# alimentadorV3.net
KiCad netlist of a schematic drawn in EAGLE
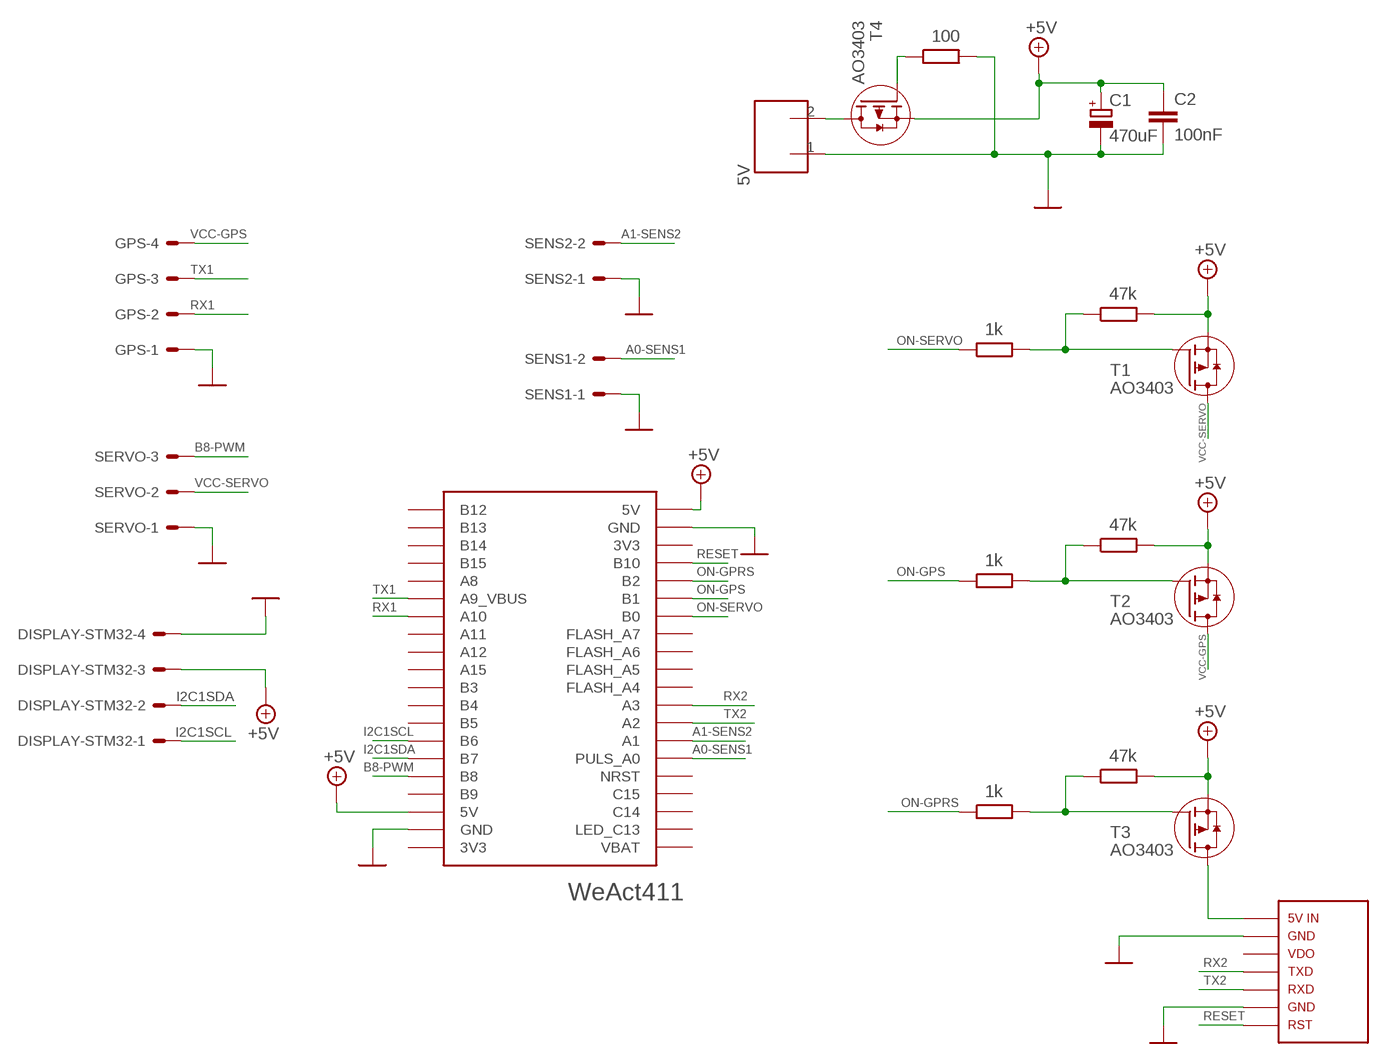
[diagram p0: schematic, sheet 1]

(export (version "E")
  (design (tool "Eeschema 10.0.6"))
  (components
    (comp (ref "5V")
      (value "CONECTOR_2P-3.81")
      (footprint "eagle-import:CON2P-3.81")
      (libsource (lib "eagle-import") (part "CONECTOR_2P-3.81"))
    )
    (comp (ref "C1")
      (value "470uF")
      (footprint "eagle-import:E5-10,5")
      (libsource (lib "eagle-import") (part "CPOL-EUE5-10.5"))
    )
    (comp (ref "C2")
      (value "100nF")
      (footprint "eagle-import:C1206")
      (libsource (lib "eagle-import") (part "C-EUC1206"))
    )
    (comp (ref "DISPLAY-STM32")
      (value "22-05-7048-04")
      (footprint "eagle-import:7395-04")
      (libsource (lib "eagle-import") (part "22-?-0405-7048"))
    )
    (comp (ref "GPS")
      (value "22-27-2041-04")
      (footprint "eagle-import:6410-04")
      (libsource (lib "eagle-import") (part "22-?-0427-2041"))
    )
    (comp (ref "R1")
      (value "47k")
      (footprint "eagle-import:R1206")
      (libsource (lib "eagle-import") (part "R-EU_R1206"))
    )
    (comp (ref "R2")
      (value "47k")
      (footprint "eagle-import:R1206")
      (libsource (lib "eagle-import") (part "R-EU_R1206"))
    )
    (comp (ref "R3")
      (value "1k")
      (footprint "eagle-import:R1206")
      (libsource (lib "eagle-import") (part "R-EU_R1206"))
    )
    (comp (ref "R4")
      (value "1k")
      (footprint "eagle-import:R1206")
      (libsource (lib "eagle-import") (part "R-EU_R1206"))
    )
    (comp (ref "R5")
      (value "47k")
      (footprint "eagle-import:R1206")
      (libsource (lib "eagle-import") (part "R-EU_R1206"))
    )
    (comp (ref "R6")
      (value "1k")
      (footprint "eagle-import:R1206")
      (libsource (lib "eagle-import") (part "R-EU_R1206"))
    )
    (comp (ref "R7")
      (value "100")
      (footprint "eagle-import:R1206")
      (libsource (lib "eagle-import") (part "R-EU_R1206"))
    )
    (comp (ref "SENS1")
      (value "22-27-2021-02")
      (footprint "eagle-import:6410-02")
      (libsource (lib "eagle-import") (part "22-?-0227-2021"))
    )
    (comp (ref "SENS2")
      (value "22-27-2021-02")
      (footprint "eagle-import:6410-02")
      (libsource (lib "eagle-import") (part "22-?-0227-2021"))
    )
    (comp (ref "SERVO")
      (value "22-27-2031-03")
      (footprint "eagle-import:6410-03")
      (libsource (lib "eagle-import") (part "22-?-0327-2031"))
    )
    (comp (ref "T1")
      (value "AO3403")
      (footprint "eagle-import:SOT23")
      (libsource (lib "eagle-import") (part "AO3403"))
    )
    (comp (ref "T2")
      (value "AO3403")
      (footprint "eagle-import:SOT23")
      (libsource (lib "eagle-import") (part "AO3403"))
    )
    (comp (ref "T3")
      (value "AO3403")
      (footprint "eagle-import:SOT23")
      (libsource (lib "eagle-import") (part "AO3403"))
    )
    (comp (ref "T4")
      (value "AO3403")
      (footprint "eagle-import:SOT23")
      (libsource (lib "eagle-import") (part "AO3403"))
    )
    (comp (ref "U$1")
      (value "SIM800L")
      (footprint "eagle-import:SIM800L")
      (libsource (lib "eagle-import") (part "SIM800L"))
    )
    (comp (ref "U$2")
      (value "WEACT411")
      (footprint "eagle-import:WEACT411")
      (libsource (lib "eagle-import") (part "WEACT411"))
    )
  )
  (nets
    (net (code "1") (name "+5V") (class "Default")
      (node (ref "C1") (pin "+") (pinfunction "+_+") (pintype "passive"))
      (node (ref "C2") (pin "1") (pinfunction "1_1") (pintype "passive"))
      (node (ref "DISPLAY-STM32") (pin "3") (pinfunction "S_3") (pintype "passive"))
      (node (ref "R1") (pin "2") (pinfunction "2_2") (pintype "passive"))
      (node (ref "R2") (pin "2") (pinfunction "2_2") (pintype "passive"))
      (node (ref "R5") (pin "2") (pinfunction "2_2") (pintype "passive"))
      (node (ref "T1") (pin "2") (pinfunction "S_2") (pintype "passive"))
      (node (ref "T2") (pin "2") (pinfunction "S_2") (pintype "passive"))
      (node (ref "T3") (pin "2") (pinfunction "S_2") (pintype "passive"))
      (node (ref "T4") (pin "2") (pinfunction "S_2") (pintype "passive"))
      (node (ref "U$2") (pin "5V@1") (pinfunction "5V_5V@1") (pintype "power_in"))
      (node (ref "U$2") (pin "5V@2") (pinfunction "5V_5V@2") (pintype "power_in"))
    )
    (net (code "2") (name "/A0-SENS1") (class "Default")
      (node (ref "SENS1") (pin "2") (pinfunction "S_2") (pintype "passive"))
      (node (ref "U$2") (pin "A0") (pinfunction "PULS_A0_A0") (pintype "bidirectional"))
    )
    (net (code "3") (name "/A1-SENS2") (class "Default")
      (node (ref "SENS2") (pin "2") (pinfunction "S_2") (pintype "passive"))
      (node (ref "U$2") (pin "A1") (pinfunction "A1_A1") (pintype "bidirectional"))
    )
    (net (code "4") (name "/B8-PWM") (class "Default")
      (node (ref "SERVO") (pin "3") (pinfunction "S_3") (pintype "passive"))
      (node (ref "U$2") (pin "B8") (pinfunction "B8_B8") (pintype "bidirectional"))
    )
    (net (code "5") (name "/I2C1SCL") (class "Default")
      (node (ref "DISPLAY-STM32") (pin "1") (pinfunction "S_1") (pintype "passive"))
      (node (ref "U$2") (pin "B6") (pinfunction "B6_B6") (pintype "bidirectional"))
    )
    (net (code "6") (name "/I2C1SDA") (class "Default")
      (node (ref "DISPLAY-STM32") (pin "2") (pinfunction "S_2") (pintype "passive"))
      (node (ref "U$2") (pin "B7") (pinfunction "B7_B7") (pintype "bidirectional"))
    )
    (net (code "7") (name "/ON-GPRS") (class "Default")
      (node (ref "R6") (pin "1") (pinfunction "1_1") (pintype "passive"))
      (node (ref "U$2") (pin "B2") (pinfunction "B2_B2") (pintype "bidirectional"))
    )
    (net (code "8") (name "/ON-GPS") (class "Default")
      (node (ref "R4") (pin "1") (pinfunction "1_1") (pintype "passive"))
      (node (ref "U$2") (pin "B1") (pinfunction "B1_B1") (pintype "bidirectional"))
    )
    (net (code "9") (name "/ON-SERVO") (class "Default")
      (node (ref "R3") (pin "1") (pinfunction "1_1") (pintype "passive"))
      (node (ref "U$2") (pin "B0") (pinfunction "B0_B0") (pintype "bidirectional"))
    )
    (net (code "10") (name "/RESET") (class "Default")
      (node (ref "U$1") (pin "RST") (pinfunction "RST_RST") (pintype "input"))
      (node (ref "U$2") (pin "B10") (pinfunction "B10_B10") (pintype "bidirectional"))
    )
    (net (code "11") (name "/RX1") (class "Default")
      (node (ref "GPS") (pin "2") (pinfunction "S_2") (pintype "passive"))
      (node (ref "U$2") (pin "A10") (pinfunction "A10_A10") (pintype "bidirectional"))
    )
    (net (code "12") (name "/RX2") (class "Default")
      (node (ref "U$1") (pin "TXD") (pinfunction "TXD_TXD") (pintype "output"))
      (node (ref "U$2") (pin "A3") (pinfunction "A3_A3") (pintype "bidirectional"))
    )
    (net (code "13") (name "/TX1") (class "Default")
      (node (ref "GPS") (pin "3") (pinfunction "S_3") (pintype "passive"))
      (node (ref "U$2") (pin "A9") (pinfunction "A9_VBUS_A9") (pintype "bidirectional"))
    )
    (net (code "14") (name "/TX2") (class "Default")
      (node (ref "U$1") (pin "RXD") (pinfunction "RXD_RXD") (pintype "input"))
      (node (ref "U$2") (pin "A2") (pinfunction "A2_A2") (pintype "bidirectional"))
    )
    (net (code "15") (name "/VBAT") (class "Default")
      (node (ref "U$2") (pin "VBAT") (pinfunction "VBAT_VBAT") (pintype "power_in"))
    )
    (net (code "16") (name "/VCC-GPS") (class "Default")
      (node (ref "GPS") (pin "4") (pinfunction "S_4") (pintype "passive"))
      (node (ref "T2") (pin "3") (pinfunction "D_3") (pintype "passive"))
    )
    (net (code "17") (name "/VCC-SERVO") (class "Default")
      (node (ref "SERVO") (pin "2") (pinfunction "S_2") (pintype "passive"))
      (node (ref "T1") (pin "3") (pinfunction "D_3") (pintype "passive"))
    )
    (net (code "18") (name "/VDO") (class "Default")
      (node (ref "U$1") (pin "VDO") (pinfunction "VDO_VDO") (pintype "power_in"))
    )
    (net (code "19") (name "GND") (class "Default")
      (node (ref "5V") (pin "1") (pinfunction "1_1") (pintype "bidirectional"))
      (node (ref "C1") (pin "-") (pinfunction "-_-") (pintype "passive"))
      (node (ref "C2") (pin "2") (pinfunction "2_2") (pintype "passive"))
      (node (ref "DISPLAY-STM32") (pin "4") (pinfunction "S_4") (pintype "passive"))
      (node (ref "GPS") (pin "1") (pinfunction "S_1") (pintype "passive"))
      (node (ref "R7") (pin "2") (pinfunction "2_2") (pintype "passive"))
      (node (ref "SENS1") (pin "1") (pinfunction "S_1") (pintype "passive"))
      (node (ref "SENS2") (pin "1") (pinfunction "S_1") (pintype "passive"))
      (node (ref "SERVO") (pin "1") (pinfunction "S_1") (pintype "passive"))
      (node (ref "U$1") (pin "GND@0") (pinfunction "GND_GND@0") (pintype "power_in"))
      (node (ref "U$1") (pin "GND@1") (pinfunction "GND_GND@1") (pintype "power_in"))
      (node (ref "U$2") (pin "GND@1") (pinfunction "GND_GND@1") (pintype "power_in"))
      (node (ref "U$2") (pin "GND@2") (pinfunction "GND_GND@2") (pintype "power_in"))
    )
    (net (code "20") (name "Net-(T1-G)") (class "Default")
      (node (ref "R2") (pin "1") (pinfunction "1_1") (pintype "passive"))
      (node (ref "R3") (pin "2") (pinfunction "2_2") (pintype "passive"))
      (node (ref "T1") (pin "1") (pinfunction "G_1") (pintype "passive"))
    )
    (net (code "21") (name "Net-(T2-G)") (class "Default")
      (node (ref "R1") (pin "1") (pinfunction "1_1") (pintype "passive"))
      (node (ref "R4") (pin "2") (pinfunction "2_2") (pintype "passive"))
      (node (ref "T2") (pin "1") (pinfunction "G_1") (pintype "passive"))
    )
    (net (code "22") (name "Net-(T3-D)") (class "Default")
      (node (ref "T3") (pin "3") (pinfunction "D_3") (pintype "passive"))
      (node (ref "U$1") (pin "5VIN") (pinfunction "5VIN_5VIN") (pintype "power_in"))
    )
    (net (code "23") (name "Net-(T3-G)") (class "Default")
      (node (ref "R5") (pin "1") (pinfunction "1_1") (pintype "passive"))
      (node (ref "R6") (pin "2") (pinfunction "2_2") (pintype "passive"))
      (node (ref "T3") (pin "1") (pinfunction "G_1") (pintype "passive"))
    )
    (net (code "24") (name "Net-(T4-D)") (class "Default")
      (node (ref "5V") (pin "2") (pinfunction "2_2") (pintype "bidirectional"))
      (node (ref "T4") (pin "3") (pinfunction "D_3") (pintype "passive"))
    )
    (net (code "25") (name "Net-(T4-G)") (class "Default")
      (node (ref "R7") (pin "1") (pinfunction "1_1") (pintype "passive"))
      (node (ref "T4") (pin "1") (pinfunction "G_1") (pintype "passive"))
    )
    (net (code "26") (name "unconnected-(U$2-3V3-Pad3V3@1)") (class "Default")
      (node (ref "U$2") (pin "3V3@1") (pinfunction "3V3_3V3@1") (pintype "bidirectional"))
    )
    (net (code "27") (name "unconnected-(U$2-3V3-Pad3V3@2)") (class "Default")
      (node (ref "U$2") (pin "3V3@2") (pinfunction "3V3_3V3@2") (pintype "bidirectional"))
    )
    (net (code "28") (name "unconnected-(U$2-FLASH_A4-PadA4)") (class "Default")
      (node (ref "U$2") (pin "A4") (pinfunction "FLASH_A4_A4") (pintype "bidirectional"))
    )
    (net (code "29") (name "unconnected-(U$2-FLASH_A5-PadA5)") (class "Default")
      (node (ref "U$2") (pin "A5") (pinfunction "FLASH_A5_A5") (pintype "bidirectional"))
    )
    (net (code "30") (name "unconnected-(U$2-FLASH_A6-PadA6)") (class "Default")
      (node (ref "U$2") (pin "A6") (pinfunction "FLASH_A6_A6") (pintype "bidirectional"))
    )
    (net (code "31") (name "unconnected-(U$2-FLASH_A7-PadA7)") (class "Default")
      (node (ref "U$2") (pin "A7") (pinfunction "FLASH_A7_A7") (pintype "bidirectional"))
    )
    (net (code "32") (name "unconnected-(U$2-LED_C13-PadC13)") (class "Default")
      (node (ref "U$2") (pin "C13") (pinfunction "LED_C13_C13") (pintype "bidirectional"))
    )
    (net (code "33") (name "unconnected-(U$2-PadA8)") (class "Default")
      (node (ref "U$2") (pin "A8") (pinfunction "A8_A8") (pintype "bidirectional"))
    )
    (net (code "34") (name "unconnected-(U$2-PadA11)") (class "Default")
      (node (ref "U$2") (pin "A11") (pinfunction "A11_A11") (pintype "bidirectional"))
    )
    (net (code "35") (name "unconnected-(U$2-PadA12)") (class "Default")
      (node (ref "U$2") (pin "A12") (pinfunction "A12_A12") (pintype "bidirectional"))
    )
    (net (code "36") (name "unconnected-(U$2-PadA15)") (class "Default")
      (node (ref "U$2") (pin "A15") (pinfunction "A15_A15") (pintype "bidirectional"))
    )
    (net (code "37") (name "unconnected-(U$2-PadB3)") (class "Default")
      (node (ref "U$2") (pin "B3") (pinfunction "B3_B3") (pintype "bidirectional"))
    )
    (net (code "38") (name "unconnected-(U$2-PadB4)") (class "Default")
      (node (ref "U$2") (pin "B4") (pinfunction "B4_B4") (pintype "bidirectional"))
    )
    (net (code "39") (name "unconnected-(U$2-PadB5)") (class "Default")
      (node (ref "U$2") (pin "B5") (pinfunction "B5_B5") (pintype "bidirectional"))
    )
    (net (code "40") (name "unconnected-(U$2-PadB9)") (class "Default")
      (node (ref "U$2") (pin "B9") (pinfunction "B9_B9") (pintype "bidirectional"))
    )
    (net (code "41") (name "unconnected-(U$2-PadB12)") (class "Default")
      (node (ref "U$2") (pin "B12") (pinfunction "B12_B12") (pintype "bidirectional"))
    )
    (net (code "42") (name "unconnected-(U$2-PadB13)") (class "Default")
      (node (ref "U$2") (pin "B13") (pinfunction "B13_B13") (pintype "bidirectional"))
    )
    (net (code "43") (name "unconnected-(U$2-PadB14)") (class "Default")
      (node (ref "U$2") (pin "B14") (pinfunction "B14_B14") (pintype "bidirectional"))
    )
    (net (code "44") (name "unconnected-(U$2-PadB15)") (class "Default")
      (node (ref "U$2") (pin "B15") (pinfunction "B15_B15") (pintype "bidirectional"))
    )
    (net (code "45") (name "unconnected-(U$2-PadC14)") (class "Default")
      (node (ref "U$2") (pin "C14") (pinfunction "C14_C14") (pintype "bidirectional"))
    )
    (net (code "46") (name "unconnected-(U$2-PadC15)") (class "Default")
      (node (ref "U$2") (pin "C15") (pinfunction "C15_C15") (pintype "bidirectional"))
    )
    (net (code "47") (name "unconnected-(U$2-PadNRST)") (class "Default")
      (node (ref "U$2") (pin "NRST") (pinfunction "NRST_NRST") (pintype "bidirectional"))
    )
  )
)
